# USB2514_MCU.net
KiCad netlist of a schematic drawn in Altium Designer
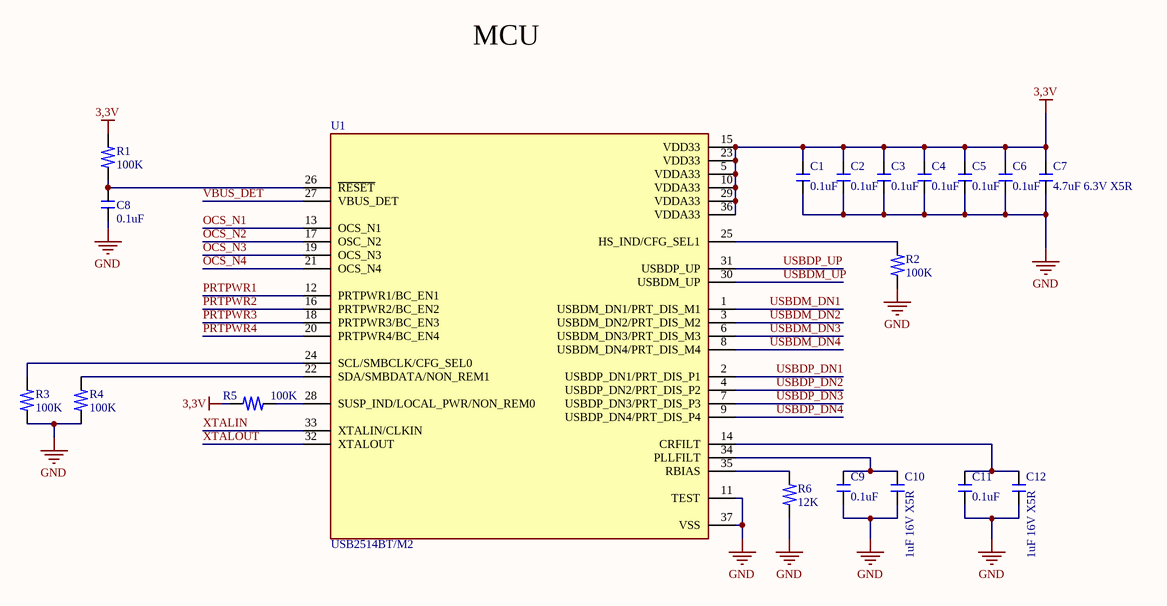
[diagram p0: USB2514 MCU.SchDoc]

(export (version "E")
  (design (tool "Eeschema 10.0.6"))
  (components
    (comp (ref "C1")
      (value "0.1uF")
      (footprint "CAPC1608X06N-0603")
      (libsource (lib "SCH_LIB") (part "CAP_0603_0.1uF"))
    )
    (comp (ref "C2")
      (value "0.1uF")
      (footprint "CAPC1608X06N-0603")
      (libsource (lib "SCH_LIB") (part "CAP_0603_0.1uF"))
    )
    (comp (ref "C3")
      (value "0.1uF")
      (footprint "CAPC1608X06N-0603")
      (libsource (lib "SCH_LIB") (part "CAP_0603_0.1uF"))
    )
    (comp (ref "C4")
      (value "0.1uF")
      (footprint "CAPC1608X06N-0603")
      (libsource (lib "SCH_LIB") (part "CAP_0603_0.1uF"))
    )
    (comp (ref "C5")
      (value "0.1uF")
      (footprint "CAPC1608X06N-0603")
      (libsource (lib "SCH_LIB") (part "CAP_0603_0.1uF"))
    )
    (comp (ref "C6")
      (value "0.1uF")
      (footprint "CAPC1608X06N-0603")
      (libsource (lib "SCH_LIB") (part "CAP_0603_0.1uF"))
    )
    (comp (ref "C7")
      (value "4.7uF 6.3V X5R")
      (footprint "CAPC1608X06N-0603")
      (libsource (lib "SCH_LIB") (part "CAP_0603_0.1uF"))
    )
    (comp (ref "C8")
      (value "0.1uF")
      (footprint "CAPC1608X06N-0603")
      (libsource (lib "SCH_LIB") (part "CAP_0603_0.1uF"))
    )
    (comp (ref "C9")
      (value "0.1uF")
      (footprint "CAPC1608X06N-0603")
      (libsource (lib "SCH_LIB") (part "CAP_0603_0.1uF"))
    )
    (comp (ref "C10")
      (value "1uF 16V X5R")
      (footprint "CAPC1608X06N-0603")
      (libsource (lib "SCH_LIB") (part "CAP_0603_0.1uF"))
    )
    (comp (ref "C11")
      (value "0.1uF")
      (footprint "CAPC1608X06N-0603")
      (libsource (lib "SCH_LIB") (part "CAP_0603_0.1uF"))
    )
    (comp (ref "C12")
      (value "1uF 16V X5R")
      (footprint "CAPC1608X06N-0603")
      (libsource (lib "SCH_LIB") (part "CAP_0603_0.1uF"))
    )
    (comp (ref "R1")
      (value "100K")
      (footprint "RESC1608X06N-0603")
      (libsource (lib "SCH_LIB") (part "RES_0603_10K"))
    )
    (comp (ref "R2")
      (value "100K")
      (footprint "RESC1608X06N-0603")
      (libsource (lib "SCH_LIB") (part "RES_0603_10K"))
    )
    (comp (ref "R3")
      (value "100K")
      (footprint "RESC1608X06N-0603")
      (libsource (lib "SCH_LIB") (part "RES_0603_10K"))
    )
    (comp (ref "R4")
      (value "100K")
      (footprint "RESC1608X06N-0603")
      (libsource (lib "SCH_LIB") (part "RES_0603_10K"))
    )
    (comp (ref "R5")
      (value "100K")
      (footprint "RESC1608X06N-0603")
      (libsource (lib "") (part "RES_0603_10K_1"))
    )
    (comp (ref "R6")
      (value "12K")
      (footprint "RESC1608X06N-0603")
      (libsource (lib "SCH_LIB") (part "RES_0603_10K"))
    )
    (comp (ref "U1")
      (value "USB2514BT/M2")
      (footprint "QFN50P600X600X100_HS-37N")
      (description "USB Hub Controller USB Interface 36-SQFN (6x6)")
      (fields (field (name "MF") "Microchip"))
      (libsource (lib "SCH_LIB") (part "USB2514BT/M2"))
    )
  )
  (nets
    (net (code "1") (name "/OCS_N1") (class "Default")
      (node (ref "U1") (pin "13") (pinfunction "OCS_N1_13") (pintype "passive"))
    )
    (net (code "2") (name "/OCS_N2") (class "Default")
      (node (ref "U1") (pin "17") (pinfunction "OSC_N2_17") (pintype "passive"))
    )
    (net (code "3") (name "/OCS_N3") (class "Default")
      (node (ref "U1") (pin "19") (pinfunction "OCS_N3_19") (pintype "passive"))
    )
    (net (code "4") (name "/OCS_N4") (class "Default")
      (node (ref "U1") (pin "21") (pinfunction "OCS_N4_21") (pintype "passive"))
    )
    (net (code "5") (name "/PRTPWR1") (class "Default")
      (node (ref "U1") (pin "12") (pinfunction "PRTPWR1/BC_EN1_12") (pintype "passive"))
    )
    (net (code "6") (name "/PRTPWR2") (class "Default")
      (node (ref "U1") (pin "16") (pinfunction "PRTPWR2/BC_EN2_16") (pintype "passive"))
    )
    (net (code "7") (name "/PRTPWR3") (class "Default")
      (node (ref "U1") (pin "18") (pinfunction "PRTPWR3/BC_EN3_18") (pintype "passive"))
    )
    (net (code "8") (name "/PRTPWR4") (class "Default")
      (node (ref "U1") (pin "20") (pinfunction "PRTPWR4/BC_EN4_20") (pintype "passive"))
    )
    (net (code "9") (name "/USBDM_DN1") (class "Default")
      (node (ref "U1") (pin "1") (pinfunction "USBDM_DN1/PRT_DIS_M1_1") (pintype "passive"))
    )
    (net (code "10") (name "/USBDM_DN2") (class "Default")
      (node (ref "U1") (pin "3") (pinfunction "USBDM_DN2/PRT_DIS_M2_3") (pintype "passive"))
    )
    (net (code "11") (name "/USBDM_DN3") (class "Default")
      (node (ref "U1") (pin "6") (pinfunction "USBDM_DN3/PRT_DIS_M3_6") (pintype "passive"))
    )
    (net (code "12") (name "/USBDM_DN4") (class "Default")
      (node (ref "U1") (pin "8") (pinfunction "USBDM_DN4/PRT_DIS_M4_8") (pintype "passive"))
    )
    (net (code "13") (name "/USBDM_UP") (class "Default")
      (node (ref "U1") (pin "30") (pinfunction "USBDM_UP_30") (pintype "passive"))
    )
    (net (code "14") (name "/USBDP_DN1") (class "Default")
      (node (ref "U1") (pin "2") (pinfunction "USBDP_DN1/PRT_DIS_P1_2") (pintype "passive"))
    )
    (net (code "15") (name "/USBDP_DN2") (class "Default")
      (node (ref "U1") (pin "4") (pinfunction "USBDP_DN2/PRT_DIS_P2_4") (pintype "passive"))
    )
    (net (code "16") (name "/USBDP_DN3") (class "Default")
      (node (ref "U1") (pin "7") (pinfunction "USBDP_DN3/PRT_DIS_P3_7") (pintype "passive"))
    )
    (net (code "17") (name "/USBDP_DN4") (class "Default")
      (node (ref "U1") (pin "9") (pinfunction "USBDP_DN4/PRT_DIS_P4_9") (pintype "passive"))
    )
    (net (code "18") (name "/USBDP_UP") (class "Default")
      (node (ref "U1") (pin "31") (pinfunction "USBDP_UP_31") (pintype "passive"))
    )
    (net (code "19") (name "/VBUS_DET") (class "Default")
      (node (ref "U1") (pin "27") (pinfunction "VBUS_DET_27") (pintype "passive"))
    )
    (net (code "20") (name "/XTALIN") (class "Default")
      (node (ref "U1") (pin "33") (pinfunction "XTALIN/CLKIN_33") (pintype "passive"))
    )
    (net (code "21") (name "/XTALOUT") (class "Default")
      (node (ref "U1") (pin "32") (pinfunction "XTALOUT_32") (pintype "passive"))
    )
    (net (code "22") (name "3,3V") (class "Default")
      (node (ref "C1") (pin "2") (pinfunction "2_2") (pintype "passive"))
      (node (ref "C2") (pin "2") (pinfunction "2_2") (pintype "passive"))
      (node (ref "C3") (pin "2") (pinfunction "2_2") (pintype "passive"))
      (node (ref "C4") (pin "2") (pinfunction "2_2") (pintype "passive"))
      (node (ref "C5") (pin "2") (pinfunction "2_2") (pintype "passive"))
      (node (ref "C6") (pin "2") (pinfunction "2_2") (pintype "passive"))
      (node (ref "C7") (pin "2") (pinfunction "2_2") (pintype "passive"))
      (node (ref "R1") (pin "2") (pinfunction "2_2") (pintype "passive"))
      (node (ref "R5") (pin "2") (pinfunction "2_2") (pintype "passive"))
      (node (ref "U1") (pin "10") (pinfunction "VDDA33_10") (pintype "passive"))
      (node (ref "U1") (pin "15") (pinfunction "VDD33_15") (pintype "passive"))
      (node (ref "U1") (pin "23") (pinfunction "VDD33_23") (pintype "passive"))
      (node (ref "U1") (pin "29") (pinfunction "VDDA33_29") (pintype "passive"))
      (node (ref "U1") (pin "36") (pinfunction "VDDA33_36") (pintype "passive"))
      (node (ref "U1") (pin "5") (pinfunction "VDDA33_5") (pintype "passive"))
    )
    (net (code "23") (name "GND") (class "Default")
      (node (ref "C1") (pin "1") (pinfunction "1_1") (pintype "passive"))
      (node (ref "C10") (pin "1") (pinfunction "1_1") (pintype "passive"))
      (node (ref "C11") (pin "1") (pinfunction "1_1") (pintype "passive"))
      (node (ref "C12") (pin "1") (pinfunction "1_1") (pintype "passive"))
      (node (ref "C2") (pin "1") (pinfunction "1_1") (pintype "passive"))
      (node (ref "C3") (pin "1") (pinfunction "1_1") (pintype "passive"))
      (node (ref "C4") (pin "1") (pinfunction "1_1") (pintype "passive"))
      (node (ref "C5") (pin "1") (pinfunction "1_1") (pintype "passive"))
      (node (ref "C6") (pin "1") (pinfunction "1_1") (pintype "passive"))
      (node (ref "C7") (pin "1") (pinfunction "1_1") (pintype "passive"))
      (node (ref "C8") (pin "1") (pinfunction "1_1") (pintype "passive"))
      (node (ref "C9") (pin "1") (pinfunction "1_1") (pintype "passive"))
      (node (ref "R2") (pin "1") (pinfunction "1_1") (pintype "passive"))
      (node (ref "R3") (pin "1") (pinfunction "1_1") (pintype "passive"))
      (node (ref "R4") (pin "1") (pinfunction "1_1") (pintype "passive"))
      (node (ref "R6") (pin "1") (pinfunction "1_1") (pintype "passive"))
      (node (ref "U1") (pin "11") (pinfunction "TEST_11") (pintype "passive"))
      (node (ref "U1") (pin "37") (pinfunction "VSS_37") (pintype "passive"))
    )
    (net (code "24") (name "Net-(U1-CRFILT)") (class "Default")
      (node (ref "C11") (pin "2") (pinfunction "2_2") (pintype "passive"))
      (node (ref "C12") (pin "2") (pinfunction "2_2") (pintype "passive"))
      (node (ref "U1") (pin "14") (pinfunction "CRFILT_14") (pintype "passive"))
    )
    (net (code "25") (name "Net-(U1-HS_IND{slash}CFG_SEL1)") (class "Default")
      (node (ref "R2") (pin "2") (pinfunction "2_2") (pintype "passive"))
      (node (ref "U1") (pin "25") (pinfunction "HS_IND/CFG_SEL1_25") (pintype "passive"))
    )
    (net (code "26") (name "Net-(U1-PLLFILT)") (class "Default")
      (node (ref "C10") (pin "2") (pinfunction "2_2") (pintype "passive"))
      (node (ref "C9") (pin "2") (pinfunction "2_2") (pintype "passive"))
      (node (ref "U1") (pin "34") (pinfunction "PLLFILT_34") (pintype "passive"))
    )
    (net (code "27") (name "Net-(U1-RBIAS)") (class "Default")
      (node (ref "R6") (pin "2") (pinfunction "2_2") (pintype "passive"))
      (node (ref "U1") (pin "35") (pinfunction "RBIAS_35") (pintype "passive"))
    )
    (net (code "28") (name "Net-(U1-SCL{slash}SMBCLK{slash}CFG_SEL0)") (class "Default")
      (node (ref "R3") (pin "2") (pinfunction "2_2") (pintype "passive"))
      (node (ref "U1") (pin "24") (pinfunction "SCL/SMBCLK/CFG_SEL0_24") (pintype "passive"))
    )
    (net (code "29") (name "Net-(U1-SDA{slash}SMBDATA{slash}NON_REM1)") (class "Default")
      (node (ref "R4") (pin "2") (pinfunction "2_2") (pintype "passive"))
      (node (ref "U1") (pin "22") (pinfunction "SDA/SMBDATA/NON_REM1_22") (pintype "passive"))
    )
    (net (code "30") (name "Net-(U1-SUSP_IND{slash}LOCAL_PWR{slash}NON_REM0)") (class "Default")
      (node (ref "R5") (pin "1") (pinfunction "1_1") (pintype "passive"))
      (node (ref "U1") (pin "28") (pinfunction "SUSP_IND/LOCAL_PWR/NON_REM0_28") (pintype "passive"))
    )
    (net (code "31") (name "Net-(U1-~{RESET})") (class "Default")
      (node (ref "C8") (pin "2") (pinfunction "2_2") (pintype "passive"))
      (node (ref "R1") (pin "1") (pinfunction "1_1") (pintype "passive"))
      (node (ref "U1") (pin "26") (pinfunction "~{RESET}_26") (pintype "passive"))
    )
  )
)
